# Power.net
KiCad netlist of a schematic drawn in Altium Designer
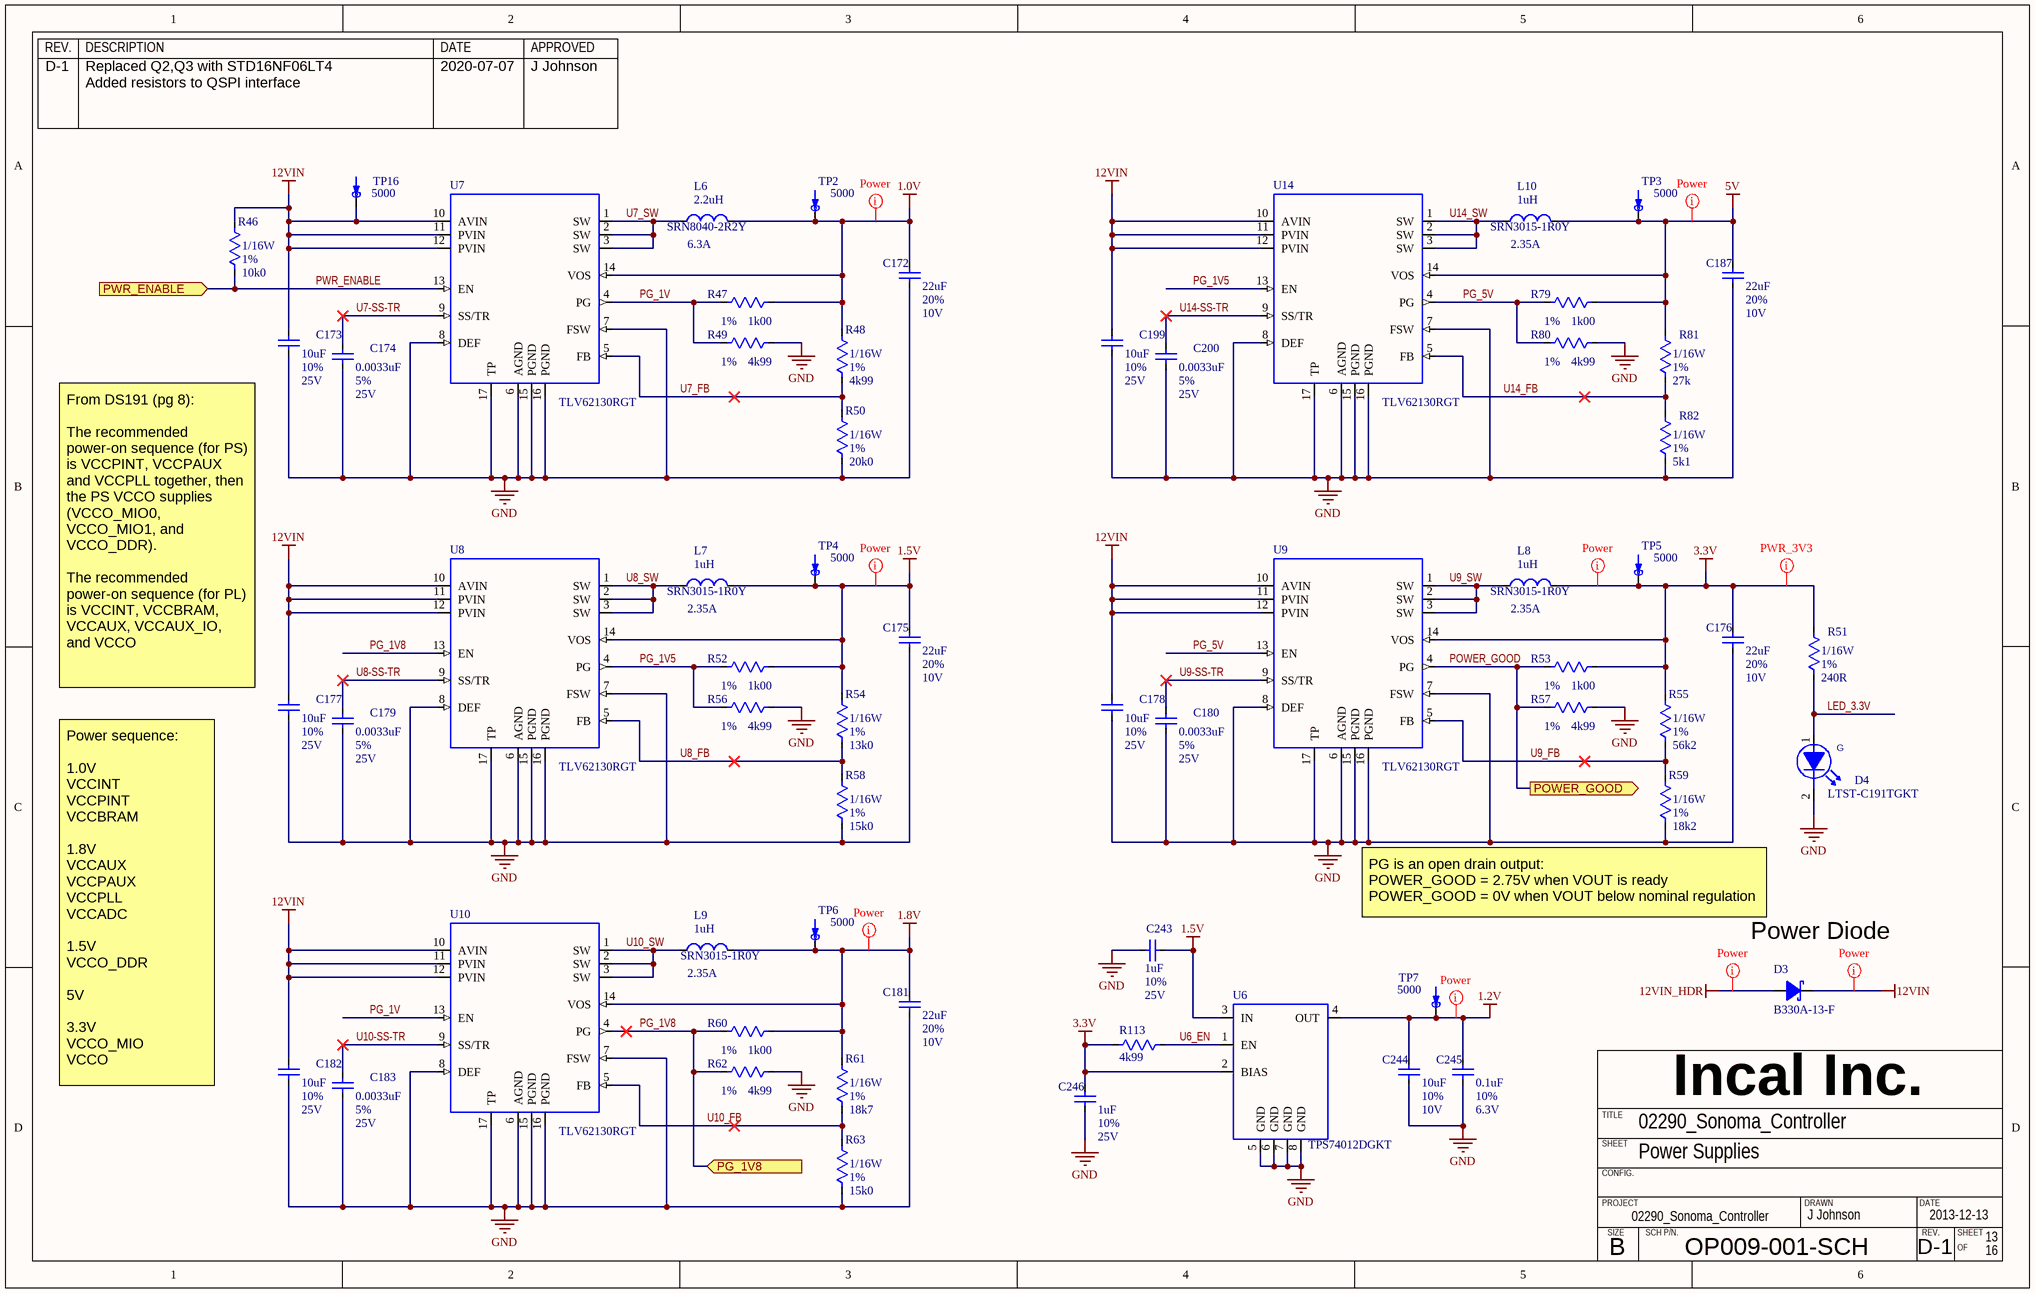
[diagram p0: Power.SchDoc]

(export (version "E")
  (design (tool "Eeschema 10.0.6"))
  (components
    (comp (ref "C172")
      (value "22uF")
      (footprint "CAPC2013X125N")
      (description "Capacitor ceramic, X5R, 22uF, 10V, 20%, -55 to +85 C, EIA0805")
      (fields
        (field (name "TOLERANCE") "20%")
        (field (name "VOLTAGE") "10V")
        (field (name "Comment") "CAPACITOR_NP_TYPE1")
      )
      (libsource (lib "parts") (part "CAPACITOR_NP_TYPE1"))
    )
    (comp (ref "C173")
      (value "10uF")
      (footprint "CAPC3216X127N")
      (description "Capacitor ceramic, X5R, 10uF, 25V, 10%, -55 to +125 C, EIA1206")
      (fields
        (field (name "TOLERANCE") "10%")
        (field (name "VOLTAGE") "25V")
        (field (name "Comment") "CAPACITOR_NP_TYPE1")
      )
      (libsource (lib "parts") (part "CAPACITOR_NP_TYPE1"))
    )
    (comp (ref "C174")
      (value "0.0033uF")
      (footprint "CAPC1005X55N")
      (description "Capacitor ceramic, X7R, 0.0033uF, 25V, 5%, -55 to +85 C, EIA0402")
      (fields
        (field (name "TOLERANCE") "5%")
        (field (name "VOLTAGE") "25V")
        (field (name "Comment") "CAPACITOR_NP_TYPE1")
      )
      (libsource (lib "parts") (part "CAPACITOR_NP_TYPE1"))
    )
    (comp (ref "C175")
      (value "22uF")
      (footprint "CAPC2013X125N")
      (description "Capacitor ceramic, X5R, 22uF, 10V, 20%, -55 to +85 C, EIA0805")
      (fields
        (field (name "TOLERANCE") "20%")
        (field (name "VOLTAGE") "10V")
        (field (name "Comment") "CAPACITOR_NP_TYPE1")
      )
      (libsource (lib "parts") (part "CAPACITOR_NP_TYPE1"))
    )
    (comp (ref "C176")
      (value "22uF")
      (footprint "CAPC2013X125N")
      (description "Capacitor ceramic, X5R, 22uF, 10V, 20%, -55 to +85 C, EIA0805")
      (fields
        (field (name "TOLERANCE") "20%")
        (field (name "VOLTAGE") "10V")
        (field (name "Comment") "CAPACITOR_NP_TYPE1")
      )
      (libsource (lib "parts") (part "CAPACITOR_NP_TYPE1"))
    )
    (comp (ref "C177")
      (value "10uF")
      (footprint "CAPC3216X127N")
      (description "Capacitor ceramic, X5R, 10uF, 25V, 10%, -55 to +125 C, EIA1206")
      (fields
        (field (name "TOLERANCE") "10%")
        (field (name "VOLTAGE") "25V")
        (field (name "Comment") "CAPACITOR_NP_TYPE1")
      )
      (libsource (lib "parts") (part "CAPACITOR_NP_TYPE1"))
    )
    (comp (ref "C178")
      (value "10uF")
      (footprint "CAPC3216X127N")
      (description "Capacitor ceramic, X5R, 10uF, 25V, 10%, -55 to +125 C, EIA1206")
      (fields
        (field (name "TOLERANCE") "10%")
        (field (name "VOLTAGE") "25V")
        (field (name "Comment") "CAPACITOR_NP_TYPE1")
      )
      (libsource (lib "parts") (part "CAPACITOR_NP_TYPE1"))
    )
    (comp (ref "C179")
      (value "0.0033uF")
      (footprint "CAPC1005X55N")
      (description "Capacitor ceramic, X7R, 0.0033uF, 25V, 5%, -55 to +85 C, EIA0402")
      (fields
        (field (name "TOLERANCE") "5%")
        (field (name "VOLTAGE") "25V")
        (field (name "Comment") "CAPACITOR_NP_TYPE1")
      )
      (libsource (lib "parts") (part "CAPACITOR_NP_TYPE1"))
    )
    (comp (ref "C180")
      (value "0.0033uF")
      (footprint "CAPC1005X55N")
      (description "Capacitor ceramic, X7R, 0.0033uF, 25V, 5%, -55 to +85 C, EIA0402")
      (fields
        (field (name "TOLERANCE") "5%")
        (field (name "VOLTAGE") "25V")
        (field (name "Comment") "CAPACITOR_NP_TYPE1")
      )
      (libsource (lib "parts") (part "CAPACITOR_NP_TYPE1"))
    )
    (comp (ref "C181")
      (value "22uF")
      (footprint "CAPC2013X125N")
      (description "Capacitor ceramic, X5R, 22uF, 10V, 20%, -55 to +85 C, EIA0805")
      (fields
        (field (name "TOLERANCE") "20%")
        (field (name "VOLTAGE") "10V")
        (field (name "Comment") "CAPACITOR_NP_TYPE1")
      )
      (libsource (lib "parts") (part "CAPACITOR_NP_TYPE1"))
    )
    (comp (ref "C182")
      (value "10uF")
      (footprint "CAPC3216X127N")
      (description "Capacitor ceramic, X5R, 10uF, 25V, 10%, -55 to +125 C, EIA1206")
      (fields
        (field (name "TOLERANCE") "10%")
        (field (name "VOLTAGE") "25V")
        (field (name "Comment") "CAPACITOR_NP_TYPE1")
      )
      (libsource (lib "parts") (part "CAPACITOR_NP_TYPE1"))
    )
    (comp (ref "C183")
      (value "0.0033uF")
      (footprint "CAPC1005X55N")
      (description "Capacitor ceramic, X7R, 0.0033uF, 25V, 5%, -55 to +85 C, EIA0402")
      (fields
        (field (name "TOLERANCE") "5%")
        (field (name "VOLTAGE") "25V")
        (field (name "Comment") "CAPACITOR_NP_TYPE1")
      )
      (libsource (lib "parts") (part "CAPACITOR_NP_TYPE1"))
    )
    (comp (ref "C187")
      (value "22uF")
      (footprint "CAPC2013X125N")
      (description "Capacitor ceramic, X5R, 22uF, 10V, 20%, -55 to +85 C, EIA0805")
      (fields
        (field (name "TOLERANCE") "20%")
        (field (name "VOLTAGE") "10V")
        (field (name "Comment") "CAPACITOR_NP_TYPE1")
      )
      (libsource (lib "parts") (part "CAPACITOR_NP_TYPE1"))
    )
    (comp (ref "C199")
      (value "10uF")
      (footprint "CAPC3216X127N")
      (description "Capacitor ceramic, X5R, 10uF, 25V, 10%, -55 to +125 C, EIA1206")
      (fields
        (field (name "TOLERANCE") "10%")
        (field (name "VOLTAGE") "25V")
        (field (name "Comment") "CAPACITOR_NP_TYPE1")
      )
      (libsource (lib "parts") (part "CAPACITOR_NP_TYPE1"))
    )
    (comp (ref "C200")
      (value "0.0033uF")
      (footprint "CAPC1005X55N")
      (description "Capacitor ceramic, X7R, 0.0033uF, 25V, 5%, -55 to +85 C, EIA0402")
      (fields
        (field (name "TOLERANCE") "5%")
        (field (name "VOLTAGE") "25V")
        (field (name "Comment") "CAPACITOR_NP_TYPE1")
      )
      (libsource (lib "parts") (part "CAPACITOR_NP_TYPE1"))
    )
    (comp (ref "C243")
      (value "1uF")
      (footprint "CAPC1608X38N")
      (description "Capacitor ceramic, X5R, 1uF, 25V, 10%, -55 to +85 C, EIA(M)1608")
      (fields
        (field (name "TOLERANCE") "10%")
        (field (name "VOLTAGE") "25V")
        (field (name "Comment") "CAPACITOR_NP_TYPE1")
      )
      (libsource (lib "parts") (part "CAPACITOR_NP_TYPE1"))
    )
    (comp (ref "C244")
      (value "10uF")
      (footprint "CAPC1608X38N")
      (description "Capacitor ceramic, X5R, 10uF, 10V, 10%, -55 to +85 C, EIA0603")
      (fields
        (field (name "TOLERANCE") "10%")
        (field (name "VOLTAGE") "10V")
        (field (name "Comment") "CAPACITOR_NP_TYPE1")
      )
      (libsource (lib "parts") (part "CAPACITOR_NP_TYPE1"))
    )
    (comp (ref "C245")
      (value "0.1uF")
      (footprint "CAPC0603X33N")
      (description "Capacitor ceramic, X5R, 0.1uF, 6.3V, 10%, -55 to +125 C, EIA0201")
      (fields
        (field (name "TOLERANCE") "10%")
        (field (name "VOLTAGE") "6.3V")
        (field (name "Comment") "CAPACITOR_NP_TYPE1")
      )
      (libsource (lib "parts") (part "CAPACITOR_NP_TYPE1"))
    )
    (comp (ref "C246")
      (value "1uF")
      (footprint "CAPC1608X38N")
      (description "Capacitor ceramic, X5R, 1uF, 25V, 10%, -55 to +85 C, EIA(M)1608")
      (fields
        (field (name "TOLERANCE") "10%")
        (field (name "VOLTAGE") "25V")
        (field (name "Comment") "CAPACITOR_NP_TYPE1")
      )
      (libsource (lib "parts") (part "CAPACITOR_NP_TYPE1"))
    )
    (comp (ref "D3")
      (value "DIODE_SCHOTTKY_TYPE1")
      (footprint "DIOM4629X230N")
      (description "Diode, Schottky, Vz = 30V, -55 to 125C, SMT")
      (fields (field (name "VOLTAGE") "Vz= 30V") (field (name "MFG PART NUMBER 1") "B330A-13-F"))
      (libsource (lib "parts") (part "DIODE_SCHOTTKY_TYPE1"))
    )
    (comp (ref "D4")
      (value "LED_GRN")
      (footprint "LEDM1608X38N-GRN")
      (description "Led, Green, 150mcd, SMT, LTST-C191TGKT, -20 to +80 C, 0603")
      (fields
        (field (name "POWER") "Pow")
        (field (name "VOLTAGE") "3.2V")
        (field (name "MFG PART NUMBER 1") "LTST-C191TGKT")
      )
      (libsource (lib "parts") (part "LED_GRN"))
    )
    (comp (ref "L6")
      (value "2.2uH")
      (footprint "INDM800800X400N")
      (description "Inductor, shielded, 13mOhm, 2.2uH, 6.3A, 30%, -40 to +105 C")
      (fields
        (field (name "TOLERANCE") "30%")
        (field (name "CURRENT") "6.3A")
        (field (name "MFG PART NUMBER 1") "SRN8040-2R2Y")
        (field (name "Comment") "INDUCTOR_TYPE1")
      )
      (libsource (lib "parts") (part "INDUCTOR_TYPE1"))
    )
    (comp (ref "L7")
      (value "1uH")
      (footprint "INDM300300X150N")
      (description "Inductor, shielded, 48mOhm, 1uH, 2.35A, 30%, -40 to +125 C")
      (fields
        (field (name "TOLERANCE") "30%")
        (field (name "CURRENT") "2.35A")
        (field (name "MFG PART NUMBER 1") "SRN3015-1R0Y")
        (field (name "Comment") "INDUCTOR_TYPE1")
      )
      (libsource (lib "parts") (part "INDUCTOR_TYPE1"))
    )
    (comp (ref "L8")
      (value "1uH")
      (footprint "INDM300300X150N")
      (description "Inductor, shielded, 48mOhm, 1uH, 2.35A, 30%, -40 to +125 C")
      (fields
        (field (name "TOLERANCE") "30%")
        (field (name "CURRENT") "2.35A")
        (field (name "MFG PART NUMBER 1") "SRN3015-1R0Y")
        (field (name "Comment") "INDUCTOR_TYPE1")
      )
      (libsource (lib "parts") (part "INDUCTOR_TYPE1"))
    )
    (comp (ref "L9")
      (value "1uH")
      (footprint "INDM300300X150N")
      (description "Inductor, shielded, 48mOhm, 1uH, 2.35A, 30%, -40 to +125 C")
      (fields
        (field (name "TOLERANCE") "30%")
        (field (name "CURRENT") "2.35A")
        (field (name "MFG PART NUMBER 1") "SRN3015-1R0Y")
        (field (name "Comment") "INDUCTOR_TYPE1")
      )
      (libsource (lib "parts") (part "INDUCTOR_TYPE1"))
    )
    (comp (ref "L10")
      (value "1uH")
      (footprint "INDM300300X150N")
      (description "Inductor, shielded, 48mOhm, 1uH, 2.35A, 30%, -40 to +125 C")
      (fields
        (field (name "TOLERANCE") "30%")
        (field (name "CURRENT") "2.35A")
        (field (name "MFG PART NUMBER 1") "SRN3015-1R0Y")
        (field (name "Comment") "INDUCTOR_TYPE1")
      )
      (libsource (lib "parts") (part "INDUCTOR_TYPE1"))
    )
    (comp (ref "R46")
      (value "10k0")
      (footprint "RESC1005X33N")
      (description "Resistor, 10k0, 1/16W, 1%, -55 to +155 C, EIA0402")
      (fields (field (name "VOLTAGE") "50V") (field (name "POWER") "1/16W") (field (name "TOLERANCE") "1%"))
      (libsource (lib "parts") (part "RESISTOR_TYPE1"))
    )
    (comp (ref "R47")
      (value "1k00")
      (footprint "RESC1005X33N")
      (description "Resistor, 1k00, 1/16W, 1%, -55 to +155 C, EIA0402")
      (fields (field (name "VOLTAGE") "50V") (field (name "POWER") "1/16W") (field (name "TOLERANCE") "1%"))
      (libsource (lib "parts") (part "RESISTOR_TYPE1"))
    )
    (comp (ref "R48")
      (value "4k99")
      (footprint "RESC1005X33N")
      (description "Resistor, 4k99, 1/16W, 1%, -50 to +155 C, EIA0402, EIA(M)1005")
      (fields (field (name "VOLTAGE") "50V") (field (name "POWER") "1/16W") (field (name "TOLERANCE") "1%"))
      (libsource (lib "parts") (part "RESISTOR_TYPE1"))
    )
    (comp (ref "R49")
      (value "4k99")
      (footprint "RESC1005X33N")
      (description "Resistor, 4k99, 1/16W, 1%, -50 to +155 C, EIA0402, EIA(M)1005")
      (fields (field (name "VOLTAGE") "50V") (field (name "POWER") "1/16W") (field (name "TOLERANCE") "1%"))
      (libsource (lib "parts") (part "RESISTOR_TYPE1"))
    )
    (comp (ref "R50")
      (value "20k0")
      (footprint "RESC1005X33N")
      (description "Resistor, 20k0, 1/16W, 1%, -50 to +155 C, EIA0402, EIA(M)1005")
      (fields (field (name "VOLTAGE") "50V") (field (name "POWER") "1/16W") (field (name "TOLERANCE") "1%"))
      (libsource (lib "parts") (part "RESISTOR_TYPE1"))
    )
    (comp (ref "R51")
      (value "240R")
      (footprint "RESC1005X33N")
      (description "Resistor, 240R, 1/16W, 1%, -50 to +155 C, EIA0402, EIA(M)1005")
      (fields (field (name "VOLTAGE") "50V") (field (name "POWER") "1/16W") (field (name "TOLERANCE") "1%"))
      (libsource (lib "parts") (part "RESISTOR_TYPE1"))
    )
    (comp (ref "R52")
      (value "1k00")
      (footprint "RESC1005X33N")
      (description "Resistor, 1k00, 1/16W, 1%, -55 to +155 C, EIA0402")
      (fields (field (name "VOLTAGE") "50V") (field (name "POWER") "1/16W") (field (name "TOLERANCE") "1%"))
      (libsource (lib "parts") (part "RESISTOR_TYPE1"))
    )
    (comp (ref "R53")
      (value "1k00")
      (footprint "RESC1005X33N")
      (description "Resistor, 1k00, 1/16W, 1%, -55 to +155 C, EIA0402")
      (fields (field (name "VOLTAGE") "50V") (field (name "POWER") "1/16W") (field (name "TOLERANCE") "1%"))
      (libsource (lib "parts") (part "RESISTOR_TYPE1"))
    )
    (comp (ref "R54")
      (value "13k0")
      (footprint "RESC1005X33N")
      (description "Resistor, 13k0, 1/16W, 1%, -50 to +155 C, EIA0402, EIA(M)1005")
      (fields (field (name "VOLTAGE") "50V") (field (name "POWER") "1/16W") (field (name "TOLERANCE") "1%"))
      (libsource (lib "parts") (part "RESISTOR_TYPE1"))
    )
    (comp (ref "R55")
      (value "56k2")
      (footprint "RESC1005X33N")
      (description "Resistor, 56k2, 1/16W, 1%, -50 to +155 C, EIA0402, EIA(M)1005")
      (fields (field (name "VOLTAGE") "50V") (field (name "POWER") "1/16W") (field (name "TOLERANCE") "1%"))
      (libsource (lib "parts") (part "RESISTOR_TYPE1"))
    )
    (comp (ref "R56")
      (value "4k99")
      (footprint "RESC1005X33N")
      (description "Resistor, 4k99, 1/16W, 1%, -50 to +155 C, EIA0402, EIA(M)1005")
      (fields (field (name "VOLTAGE") "50V") (field (name "POWER") "1/16W") (field (name "TOLERANCE") "1%"))
      (libsource (lib "parts") (part "RESISTOR_TYPE1"))
    )
    (comp (ref "R57")
      (value "4k99")
      (footprint "RESC1005X33N")
      (description "Resistor, 4k99, 1/16W, 1%, -50 to +155 C, EIA0402, EIA(M)1005")
      (fields (field (name "VOLTAGE") "50V") (field (name "POWER") "1/16W") (field (name "TOLERANCE") "1%"))
      (libsource (lib "parts") (part "RESISTOR_TYPE1"))
    )
    (comp (ref "R58")
      (value "15k0")
      (footprint "RESC1005X33N")
      (description "Resistor, 15k0, 1/16W, 1%, -50 to +155 C, EIA0402, EIA(M)1005")
      (fields (field (name "VOLTAGE") "50V") (field (name "POWER") "1/16W") (field (name "TOLERANCE") "1%"))
      (libsource (lib "parts") (part "RESISTOR_TYPE1"))
    )
    (comp (ref "R59")
      (value "18k2")
      (footprint "RESC1005X33N")
      (description "Resistor, 18k2, 1/16W, 1%, -50 to +155 C, EIA0402, EIA(M)1005")
      (fields (field (name "VOLTAGE") "50V") (field (name "POWER") "1/16W") (field (name "TOLERANCE") "1%"))
      (libsource (lib "parts") (part "RESISTOR_TYPE1"))
    )
    (comp (ref "R60")
      (value "1k00")
      (footprint "RESC1005X33N")
      (description "Resistor, 1k00, 1/16W, 1%, -55 to +155 C, EIA0402")
      (fields (field (name "VOLTAGE") "50V") (field (name "POWER") "1/16W") (field (name "TOLERANCE") "1%"))
      (libsource (lib "parts") (part "RESISTOR_TYPE1"))
    )
    (comp (ref "R61")
      (value "18k7")
      (footprint "RESC1005X33N")
      (description "Resistor, 18k7, 1/16W, 1%, -50 to +155 C, EIA0402, EIA(M)1005")
      (fields (field (name "VOLTAGE") "50V") (field (name "POWER") "1/16W") (field (name "TOLERANCE") "1%"))
      (libsource (lib "parts") (part "RESISTOR_TYPE1"))
    )
    (comp (ref "R62")
      (value "4k99")
      (footprint "RESC1005X33N")
      (description "Resistor, 4k99, 1/16W, 1%, -50 to +155 C, EIA0402, EIA(M)1005")
      (fields (field (name "VOLTAGE") "50V") (field (name "POWER") "1/16W") (field (name "TOLERANCE") "1%"))
      (libsource (lib "parts") (part "RESISTOR_TYPE1"))
    )
    (comp (ref "R63")
      (value "15k0")
      (footprint "RESC1005X33N")
      (description "Resistor, 15k0, 1/16W, 1%, -50 to +155 C, EIA0402, EIA(M)1005")
      (fields (field (name "VOLTAGE") "50V") (field (name "POWER") "1/16W") (field (name "TOLERANCE") "1%"))
      (libsource (lib "parts") (part "RESISTOR_TYPE1"))
    )
    (comp (ref "R79")
      (value "1k00")
      (footprint "RESC1005X33N")
      (description "Resistor, 1k00, 1/16W, 1%, -55 to +155 C, EIA0402")
      (fields (field (name "VOLTAGE") "50V") (field (name "POWER") "1/16W") (field (name "TOLERANCE") "1%"))
      (libsource (lib "parts") (part "RESISTOR_TYPE1"))
    )
    (comp (ref "R80")
      (value "4k99")
      (footprint "RESC1005X33N")
      (description "Resistor, 4k99, 1/16W, 1%, -50 to +155 C, EIA0402, EIA(M)1005")
      (fields (field (name "VOLTAGE") "50V") (field (name "POWER") "1/16W") (field (name "TOLERANCE") "1%"))
      (libsource (lib "parts") (part "RESISTOR_TYPE1"))
    )
    (comp (ref "R81")
      (value "27k")
      (footprint "RESC1005X33N")
      (description "Resistor, 27k0, 1/16W, 1%, -50 to +155 C, EIA0402, EIA(M)1005")
      (fields (field (name "VOLTAGE") "50V") (field (name "POWER") "1/16W") (field (name "TOLERANCE") "1%"))
      (libsource (lib "parts") (part "RESISTOR_TYPE1"))
    )
    (comp (ref "R82")
      (value "5k1")
      (footprint "RESC1005X33N")
      (description "Resistor, 5k10, 1/16W, 1%, -50 to +155 C, EIA0402, EIA(M)1005")
      (fields (field (name "VOLTAGE") "50V") (field (name "POWER") "1/16W") (field (name "TOLERANCE") "1%"))
      (libsource (lib "parts") (part "RESISTOR_TYPE1"))
    )
    (comp (ref "R113")
      (value "4k99")
      (footprint "RESC1005X33N")
      (description "Resistor, 4k99, 1/16W, 1%, -50 to +155 C, EIA0402, EIA(M)1005")
      (fields (field (name "VOLTAGE") "50V") (field (name "POWER") "1/16W"))
      (libsource (lib "parts") (part "RESISTOR_TYPE1"))
    )
    (comp (ref "TP2")
      (value "5000")
      (footprint "KEY_5000")
      (description "Test point bead, red, Keystone Electronics, Thru-hole,")
      (fields (field (name "POWER") "Pow") (field (name "VOLTAGE") "Vol"))
      (libsource (lib "parts") (part "TEST_POINT_TYPE4"))
    )
    (comp (ref "TP3")
      (value "5000")
      (footprint "KEY_5000")
      (description "Test point bead, red, Keystone Electronics, Thru-hole,")
      (fields (field (name "POWER") "Pow") (field (name "VOLTAGE") "Vol"))
      (libsource (lib "parts") (part "TEST_POINT_TYPE4"))
    )
    (comp (ref "TP4")
      (value "5000")
      (footprint "KEY_5000")
      (description "Test point bead, red, Keystone Electronics, Thru-hole,")
      (fields (field (name "POWER") "Pow") (field (name "VOLTAGE") "Vol"))
      (libsource (lib "parts") (part "TEST_POINT_TYPE4"))
    )
    (comp (ref "TP5")
      (value "5000")
      (footprint "KEY_5000")
      (description "Test point bead, red, Keystone Electronics, Thru-hole,")
      (fields (field (name "POWER") "Pow") (field (name "VOLTAGE") "Vol"))
      (libsource (lib "parts") (part "TEST_POINT_TYPE4"))
    )
    (comp (ref "TP6")
      (value "5000")
      (footprint "KEY_5000")
      (description "Test point bead, red, Keystone Electronics, Thru-hole,")
      (fields (field (name "POWER") "Pow") (field (name "VOLTAGE") "Vol"))
      (libsource (lib "parts") (part "TEST_POINT_TYPE4"))
    )
    (comp (ref "TP7")
      (value "5000")
      (footprint "KEY_5000")
      (description "Test point bead, red, Keystone Electronics, Thru-hole,")
      (fields (field (name "POWER") "Pow") (field (name "VOLTAGE") "Vol"))
      (libsource (lib "parts") (part "TEST_POINT_TYPE4"))
    )
    (comp (ref "TP16")
      (value "5000")
      (footprint "KEY_5000")
      (description "Test point bead, red, Keystone Electronics, Thru-hole,")
      (fields (field (name "POWER") "Pow") (field (name "VOLTAGE") "Vol"))
      (libsource (lib "parts") (part "TEST_POINT_TYPE4"))
    )
    (comp (ref "U6")
      (value "TPS740XXDGK")
      (footprint "SOP65P490X110-8N")
      (description "Fixed 1.2V LDO Regulator with Dual Input Voltages, -40 to +85 C")
      (fields (field (name "VOLTAGE") "1.2V") (field (name "MFG PART NUMBER 1") "TPS74012DGKT"))
      (libsource (lib "parts") (part "TPS740XXDGK"))
    )
    (comp (ref "U7")
      (value "TLV62130RGT")
      (footprint "QFN50P300X300X100-17N")
      (description "Step-Down Converter with DCS-Control, 4-17V 3A, 16QFN")
      (fields (field (name "VOLTAGE") "4 to 17V"))
      (libsource (lib "parts") (part "TLV62130RGT"))
    )
    (comp (ref "U8")
      (value "TLV62130RGT")
      (footprint "QFN50P300X300X100-17N")
      (description "Step-Down Converter with DCS-Control, 4-17V 3A, 16QFN")
      (fields (field (name "VOLTAGE") "4 to 17V"))
      (libsource (lib "parts") (part "TLV62130RGT"))
    )
    (comp (ref "U9")
      (value "TLV62130RGT")
      (footprint "QFN50P300X300X100-17N")
      (description "Step-Down Converter with DCS-Control, 4-17V 3A, 16QFN")
      (fields (field (name "VOLTAGE") "4 to 17V"))
      (libsource (lib "parts") (part "TLV62130RGT"))
    )
    (comp (ref "U10")
      (value "TLV62130RGT")
      (footprint "QFN50P300X300X100-17N")
      (description "Step-Down Converter with DCS-Control, 4-17V 3A, 16QFN")
      (fields (field (name "VOLTAGE") "4 to 17V"))
      (libsource (lib "parts") (part "TLV62130RGT"))
    )
    (comp (ref "U14")
      (value "TLV62130RGT")
      (footprint "QFN50P300X300X100-17N")
      (description "Step-Down Converter with DCS-Control, 4-17V 3A, 16QFN")
      (fields (field (name "VOLTAGE") "4 to 17V"))
      (libsource (lib "parts") (part "TLV62130RGT"))
    )
  )
  (nets
    (net (code "1") (name "/LED_3.3V") (class "Default")
      (node (ref "D4") (pin "1") (pinfunction "A_1") (pintype "passive"))
      (node (ref "R51") (pin "2") (pinfunction "2_2") (pintype "passive"))
    )
    (net (code "2") (name "/PG_1V") (class "Default")
      (node (ref "R47") (pin "1") (pinfunction "1_1") (pintype "passive"))
      (node (ref "R49") (pin "1") (pinfunction "1_1") (pintype "passive"))
      (node (ref "U10") (pin "13") (pinfunction "EN_13") (pintype "input"))
      (node (ref "U7") (pin "4") (pinfunction "PG_4") (pintype "output"))
    )
    (net (code "3") (name "/PG_1V5") (class "Default")
      (node (ref "R52") (pin "1") (pinfunction "1_1") (pintype "passive"))
      (node (ref "R56") (pin "1") (pinfunction "1_1") (pintype "passive"))
      (node (ref "U14") (pin "13") (pinfunction "EN_13") (pintype "input"))
      (node (ref "U8") (pin "4") (pinfunction "PG_4") (pintype "output"))
    )
    (net (code "4") (name "/PG_1V8") (class "Default")
      (node (ref "R60") (pin "1") (pinfunction "1_1") (pintype "passive"))
      (node (ref "R62") (pin "1") (pinfunction "1_1") (pintype "passive"))
      (node (ref "U10") (pin "4") (pinfunction "PG_4") (pintype "output"))
      (node (ref "U8") (pin "13") (pinfunction "EN_13") (pintype "input"))
    )
    (net (code "5") (name "/PG_5V") (class "Default")
      (node (ref "R79") (pin "1") (pinfunction "1_1") (pintype "passive"))
      (node (ref "R80") (pin "1") (pinfunction "1_1") (pintype "passive"))
      (node (ref "U14") (pin "4") (pinfunction "PG_4") (pintype "output"))
      (node (ref "U9") (pin "13") (pinfunction "EN_13") (pintype "input"))
    )
    (net (code "6") (name "/POWER_GOOD") (class "Default")
      (node (ref "R53") (pin "1") (pinfunction "1_1") (pintype "passive"))
      (node (ref "R57") (pin "1") (pinfunction "1_1") (pintype "passive"))
      (node (ref "U9") (pin "4") (pinfunction "PG_4") (pintype "output"))
    )
    (net (code "7") (name "/PWR_ENABLE") (class "Default")
      (node (ref "R46") (pin "1") (pinfunction "1_1") (pintype "passive"))
      (node (ref "U7") (pin "13") (pinfunction "EN_13") (pintype "input"))
    )
    (net (code "8") (name "/U6_EN") (class "Default")
      (node (ref "R113") (pin "1") (pinfunction "1_1") (pintype "passive"))
      (node (ref "U6") (pin "1") (pinfunction "EN_1") (pintype "power_in"))
    )
    (net (code "9") (name "/U7-SS-TR") (class "Default")
      (node (ref "C174") (pin "1") (pinfunction "1_1") (pintype "passive"))
      (node (ref "U7") (pin "9") (pinfunction "SS/TR_9") (pintype "input"))
    )
    (net (code "10") (name "/U7_FB") (class "Default")
      (node (ref "R48") (pin "1") (pinfunction "1_1") (pintype "passive"))
      (node (ref "R50") (pin "2") (pinfunction "2_2") (pintype "passive"))
      (node (ref "U7") (pin "5") (pinfunction "FB_5") (pintype "input"))
    )
    (net (code "11") (name "/U7_SW") (class "Default")
      (node (ref "L6") (pin "1") (pinfunction "1_1") (pintype "passive"))
      (node (ref "U7") (pin "1") (pinfunction "SW_1") (pintype "passive"))
      (node (ref "U7") (pin "2") (pinfunction "SW_2") (pintype "passive"))
      (node (ref "U7") (pin "3") (pinfunction "SW_3") (pintype "passive"))
    )
    (net (code "12") (name "/U8-SS-TR") (class "Default")
      (node (ref "C179") (pin "1") (pinfunction "1_1") (pintype "passive"))
      (node (ref "U8") (pin "9") (pinfunction "SS/TR_9") (pintype "input"))
    )
    (net (code "13") (name "/U8_FB") (class "Default")
      (node (ref "R54") (pin "1") (pinfunction "1_1") (pintype "passive"))
      (node (ref "R58") (pin "2") (pinfunction "2_2") (pintype "passive"))
      (node (ref "U8") (pin "5") (pinfunction "FB_5") (pintype "input"))
    )
    (net (code "14") (name "/U8_SW") (class "Default")
      (node (ref "L7") (pin "1") (pinfunction "1_1") (pintype "passive"))
      (node (ref "U8") (pin "1") (pinfunction "SW_1") (pintype "passive"))
      (node (ref "U8") (pin "2") (pinfunction "SW_2") (pintype "passive"))
      (node (ref "U8") (pin "3") (pinfunction "SW_3") (pintype "passive"))
    )
    (net (code "15") (name "/U9-SS-TR") (class "Default")
      (node (ref "C180") (pin "1") (pinfunction "1_1") (pintype "passive"))
      (node (ref "U9") (pin "9") (pinfunction "SS/TR_9") (pintype "input"))
    )
    (net (code "16") (name "/U9_FB") (class "Default")
      (node (ref "R55") (pin "1") (pinfunction "1_1") (pintype "passive"))
      (node (ref "R59") (pin "2") (pinfunction "2_2") (pintype "passive"))
      (node (ref "U9") (pin "5") (pinfunction "FB_5") (pintype "input"))
    )
    (net (code "17") (name "/U9_SW") (class "Default")
      (node (ref "L8") (pin "1") (pinfunction "1_1") (pintype "passive"))
      (node (ref "U9") (pin "1") (pinfunction "SW_1") (pintype "passive"))
      (node (ref "U9") (pin "2") (pinfunction "SW_2") (pintype "passive"))
      (node (ref "U9") (pin "3") (pinfunction "SW_3") (pintype "passive"))
    )
    (net (code "18") (name "/U10-SS-TR") (class "Default")
      (node (ref "C183") (pin "1") (pinfunction "1_1") (pintype "passive"))
      (node (ref "U10") (pin "9") (pinfunction "SS/TR_9") (pintype "input"))
    )
    (net (code "19") (name "/U10_FB") (class "Default")
      (node (ref "R61") (pin "1") (pinfunction "1_1") (pintype "passive"))
      (node (ref "R63") (pin "2") (pinfunction "2_2") (pintype "passive"))
      (node (ref "U10") (pin "5") (pinfunction "FB_5") (pintype "input"))
    )
    (net (code "20") (name "/U10_SW") (class "Default")
      (node (ref "L9") (pin "1") (pinfunction "1_1") (pintype "passive"))
      (node (ref "U10") (pin "1") (pinfunction "SW_1") (pintype "passive"))
      (node (ref "U10") (pin "2") (pinfunction "SW_2") (pintype "passive"))
      (node (ref "U10") (pin "3") (pinfunction "SW_3") (pintype "passive"))
    )
    (net (code "21") (name "/U14-SS-TR") (class "Default")
      (node (ref "C200") (pin "1") (pinfunction "1_1") (pintype "passive"))
      (node (ref "U14") (pin "9") (pinfunction "SS/TR_9") (pintype "input"))
    )
    (net (code "22") (name "/U14_FB") (class "Default")
      (node (ref "R81") (pin "1") (pinfunction "1_1") (pintype "passive"))
      (node (ref "R82") (pin "2") (pinfunction "2_2") (pintype "passive"))
      (node (ref "U14") (pin "5") (pinfunction "FB_5") (pintype "input"))
    )
    (net (code "23") (name "/U14_SW") (class "Default")
      (node (ref "L10") (pin "1") (pinfunction "1_1") (pintype "passive"))
      (node (ref "U14") (pin "1") (pinfunction "SW_1") (pintype "passive"))
      (node (ref "U14") (pin "2") (pinfunction "SW_2") (pintype "passive"))
      (node (ref "U14") (pin "3") (pinfunction "SW_3") (pintype "passive"))
    )
    (net (code "24") (name "1.0V") (class "Default")
      (node (ref "C172") (pin "1") (pinfunction "1_1") (pintype "passive"))
      (node (ref "L6") (pin "2") (pinfunction "2_2") (pintype "passive"))
      (node (ref "R47") (pin "2") (pinfunction "2_2") (pintype "passive"))
      (node (ref "R48") (pin "2") (pinfunction "2_2") (pintype "passive"))
      (node (ref "TP2") (pin "1") (pinfunction "1_1") (pintype "passive"))
      (node (ref "U7") (pin "14") (pinfunction "VOS_14") (pintype "input"))
    )
    (net (code "25") (name "1.2V") (class "Default")
      (node (ref "C244") (pin "1") (pinfunction "1_1") (pintype "passive"))
      (node (ref "C245") (pin "1") (pinfunction "1_1") (pintype "passive"))
      (node (ref "TP7") (pin "1") (pinfunction "1_1") (pintype "passive"))
      (node (ref "U6") (pin "4") (pinfunction "OUT_4") (pintype "power_in"))
    )
    (net (code "26") (name "1.5V") (class "Default")
      (node (ref "C175") (pin "1") (pinfunction "1_1") (pintype "passive"))
      (node (ref "C243") (pin "1") (pinfunction "1_1") (pintype "passive"))
      (node (ref "L7") (pin "2") (pinfunction "2_2") (pintype "passive"))
      (node (ref "R52") (pin "2") (pinfunction "2_2") (pintype "passive"))
      (node (ref "R54") (pin "2") (pinfunction "2_2") (pintype "passive"))
      (node (ref "TP4") (pin "1") (pinfunction "1_1") (pintype "passive"))
      (node (ref "U6") (pin "3") (pinfunction "IN_3") (pintype "power_in"))
      (node (ref "U8") (pin "14") (pinfunction "VOS_14") (pintype "input"))
    )
    (net (code "27") (name "1.8V") (class "Default")
      (node (ref "C181") (pin "1") (pinfunction "1_1") (pintype "passive"))
      (node (ref "L9") (pin "2") (pinfunction "2_2") (pintype "passive"))
      (node (ref "R60") (pin "2") (pinfunction "2_2") (pintype "passive"))
      (node (ref "R61") (pin "2") (pinfunction "2_2") (pintype "passive"))
      (node (ref "TP6") (pin "1") (pinfunction "1_1") (pintype "passive"))
      (node (ref "U10") (pin "14") (pinfunction "VOS_14") (pintype "input"))
    )
    (net (code "28") (name "3.3V") (class "Default")
      (node (ref "C176") (pin "1") (pinfunction "1_1") (pintype "passive"))
      (node (ref "C246") (pin "1") (pinfunction "1_1") (pintype "passive"))
      (node (ref "L8") (pin "2") (pinfunction "2_2") (pintype "passive"))
      (node (ref "R113") (pin "2") (pinfunction "2_2") (pintype "passive"))
      (node (ref "R51") (pin "1") (pinfunction "1_1") (pintype "passive"))
      (node (ref "R53") (pin "2") (pinfunction "2_2") (pintype "passive"))
      (node (ref "R55") (pin "2") (pinfunction "2_2") (pintype "passive"))
      (node (ref "TP5") (pin "1") (pinfunction "1_1") (pintype "passive"))
      (node (ref "U6") (pin "2") (pinfunction "BIAS_2") (pintype "power_in"))
      (node (ref "U9") (pin "14") (pinfunction "VOS_14") (pintype "input"))
    )
    (net (code "29") (name "5V") (class "Default")
      (node (ref "C187") (pin "1") (pinfunction "1_1") (pintype "passive"))
      (node (ref "L10") (pin "2") (pinfunction "2_2") (pintype "passive"))
      (node (ref "R79") (pin "2") (pinfunction "2_2") (pintype "passive"))
      (node (ref "R81") (pin "2") (pinfunction "2_2") (pintype "passive"))
      (node (ref "TP3") (pin "1") (pinfunction "1_1") (pintype "passive"))
      (node (ref "U14") (pin "14") (pinfunction "VOS_14") (pintype "input"))
    )
    (net (code "30") (name "12VIN") (class "Default")
      (node (ref "C173") (pin "1") (pinfunction "1_1") (pintype "passive"))
      (node (ref "C177") (pin "1") (pinfunction "1_1") (pintype "passive"))
      (node (ref "C178") (pin "1") (pinfunction "1_1") (pintype "passive"))
      (node (ref "C182") (pin "1") (pinfunction "1_1") (pintype "passive"))
      (node (ref "C199") (pin "1") (pinfunction "1_1") (pintype "passive"))
      (node (ref "D3") (pin "2") (pinfunction "K_2") (pintype "passive"))
      (node (ref "R46") (pin "2") (pinfunction "2_2") (pintype "passive"))
      (node (ref "TP16") (pin "1") (pinfunction "1_1") (pintype "passive"))
      (node (ref "U10") (pin "10") (pinfunction "AVIN_10") (pintype "power_in"))
      (node (ref "U10") (pin "11") (pinfunction "PVIN_11") (pintype "power_in"))
      (node (ref "U10") (pin "12") (pinfunction "PVIN_12") (pintype "power_in"))
      (node (ref "U14") (pin "10") (pinfunction "AVIN_10") (pintype "power_in"))
      (node (ref "U14") (pin "11") (pinfunction "PVIN_11") (pintype "power_in"))
      (node (ref "U14") (pin "12") (pinfunction "PVIN_12") (pintype "power_in"))
      (node (ref "U7") (pin "10") (pinfunction "AVIN_10") (pintype "power_in"))
      (node (ref "U7") (pin "11") (pinfunction "PVIN_11") (pintype "power_in"))
      (node (ref "U7") (pin "12") (pinfunction "PVIN_12") (pintype "power_in"))
      (node (ref "U8") (pin "10") (pinfunction "AVIN_10") (pintype "power_in"))
      (node (ref "U8") (pin "11") (pinfunction "PVIN_11") (pintype "power_in"))
      (node (ref "U8") (pin "12") (pinfunction "PVIN_12") (pintype "power_in"))
      (node (ref "U9") (pin "10") (pinfunction "AVIN_10") (pintype "power_in"))
      (node (ref "U9") (pin "11") (pinfunction "PVIN_11") (pintype "power_in"))
      (node (ref "U9") (pin "12") (pinfunction "PVIN_12") (pintype "power_in"))
    )
    (net (code "31") (name "12VIN_HDR") (class "Default")
      (node (ref "D3") (pin "1") (pinfunction "A_1") (pintype "passive"))
    )
    (net (code "32") (name "GND") (class "Default")
      (node (ref "C172") (pin "2") (pinfunction "2_2") (pintype "passive"))
      (node (ref "C173") (pin "2") (pinfunction "2_2") (pintype "passive"))
      (node (ref "C174") (pin "2") (pinfunction "2_2") (pintype "passive"))
      (node (ref "C175") (pin "2") (pinfunction "2_2") (pintype "passive"))
      (node (ref "C176") (pin "2") (pinfunction "2_2") (pintype "passive"))
      (node (ref "C177") (pin "2") (pinfunction "2_2") (pintype "passive"))
      (node (ref "C178") (pin "2") (pinfunction "2_2") (pintype "passive"))
      (node (ref "C179") (pin "2") (pinfunction "2_2") (pintype "passive"))
      (node (ref "C180") (pin "2") (pinfunction "2_2") (pintype "passive"))
      (node (ref "C181") (pin "2") (pinfunction "2_2") (pintype "passive"))
      (node (ref "C182") (pin "2") (pinfunction "2_2") (pintype "passive"))
      (node (ref "C183") (pin "2") (pinfunction "2_2") (pintype "passive"))
      (node (ref "C187") (pin "2") (pinfunction "2_2") (pintype "passive"))
      (node (ref "C199") (pin "2") (pinfunction "2_2") (pintype "passive"))
      (node (ref "C200") (pin "2") (pinfunction "2_2") (pintype "passive"))
      (node (ref "C243") (pin "2") (pinfunction "2_2") (pintype "passive"))
      (node (ref "C244") (pin "2") (pinfunction "2_2") (pintype "passive"))
      (node (ref "C245") (pin "2") (pinfunction "2_2") (pintype "passive"))
      (node (ref "C246") (pin "2") (pinfunction "2_2") (pintype "passive"))
      (node (ref "D4") (pin "2") (pinfunction "K_2") (pintype "passive"))
      (node (ref "R49") (pin "2") (pinfunction "2_2") (pintype "passive"))
      (node (ref "R50") (pin "1") (pinfunction "1_1") (pintype "passive"))
      (node (ref "R56") (pin "2") (pinfunction "2_2") (pintype "passive"))
      (node (ref "R57") (pin "2") (pinfunction "2_2") (pintype "passive"))
      (node (ref "R58") (pin "1") (pinfunction "1_1") (pintype "passive"))
      (node (ref "R59") (pin "1") (pinfunction "1_1") (pintype "passive"))
      (node (ref "R62") (pin "2") (pinfunction "2_2") (pintype "passive"))
      (node (ref "R63") (pin "1") (pinfunction "1_1") (pintype "passive"))
      (node (ref "R80") (pin "2") (pinfunction "2_2") (pintype "passive"))
      (node (ref "R82") (pin "1") (pinfunction "1_1") (pintype "passive"))
      (node (ref "U10") (pin "15") (pinfunction "PGND_15") (pintype "passive"))
      (node (ref "U10") (pin "16") (pinfunction "PGND_16") (pintype "passive"))
      (node (ref "U10") (pin "17") (pinfunction "TP_17") (pintype "passive"))
      (node (ref "U10") (pin "6") (pinfunction "AGND_6") (pintype "passive"))
      (node (ref "U10") (pin "7") (pinfunction "FSW_7") (pintype "input"))
      (node (ref "U10") (pin "8") (pinfunction "DEF_8") (pintype "input"))
      (node (ref "U14") (pin "15") (pinfunction "PGND_15") (pintype "passive"))
      (node (ref "U14") (pin "16") (pinfunction "PGND_16") (pintype "passive"))
      (node (ref "U14") (pin "17") (pinfunction "TP_17") (pintype "passive"))
      (node (ref "U14") (pin "6") (pinfunction "AGND_6") (pintype "passive"))
      (node (ref "U14") (pin "7") (pinfunction "FSW_7") (pintype "input"))
      (node (ref "U14") (pin "8") (pinfunction "DEF_8") (pintype "input"))
      (node (ref "U6") (pin "5") (pinfunction "GND_5") (pintype "power_in"))
      (node (ref "U6") (pin "6") (pinfunction "GND_6") (pintype "power_in"))
      (node (ref "U6") (pin "7") (pinfunction "GND_7") (pintype "power_in"))
      (node (ref "U6") (pin "8") (pinfunction "GND_8") (pintype "power_in"))
      (node (ref "U7") (pin "15") (pinfunction "PGND_15") (pintype "passive"))
      (node (ref "U7") (pin "16") (pinfunction "PGND_16") (pintype "passive"))
      (node (ref "U7") (pin "17") (pinfunction "TP_17") (pintype "passive"))
      (node (ref "U7") (pin "6") (pinfunction "AGND_6") (pintype "passive"))
      (node (ref "U7") (pin "7") (pinfunction "FSW_7") (pintype "input"))
      (node (ref "U7") (pin "8") (pinfunction "DEF_8") (pintype "input"))
      (node (ref "U8") (pin "15") (pinfunction "PGND_15") (pintype "passive"))
      (node (ref "U8") (pin "16") (pinfunction "PGND_16") (pintype "passive"))
      (node (ref "U8") (pin "17") (pinfunction "TP_17") (pintype "passive"))
      (node (ref "U8") (pin "6") (pinfunction "AGND_6") (pintype "passive"))
      (node (ref "U8") (pin "7") (pinfunction "FSW_7") (pintype "input"))
      (node (ref "U8") (pin "8") (pinfunction "DEF_8") (pintype "input"))
      (node (ref "U9") (pin "15") (pinfunction "PGND_15") (pintype "passive"))
      (node (ref "U9") (pin "16") (pinfunction "PGND_16") (pintype "passive"))
      (node (ref "U9") (pin "17") (pinfunction "TP_17") (pintype "passive"))
      (node (ref "U9") (pin "6") (pinfunction "AGND_6") (pintype "passive"))
      (node (ref "U9") (pin "7") (pinfunction "FSW_7") (pintype "input"))
      (node (ref "U9") (pin "8") (pinfunction "DEF_8") (pintype "input"))
    )
  )
)
